# DigitalBlad.net
KiCad netlist of a schematic drawn in Altium Designer
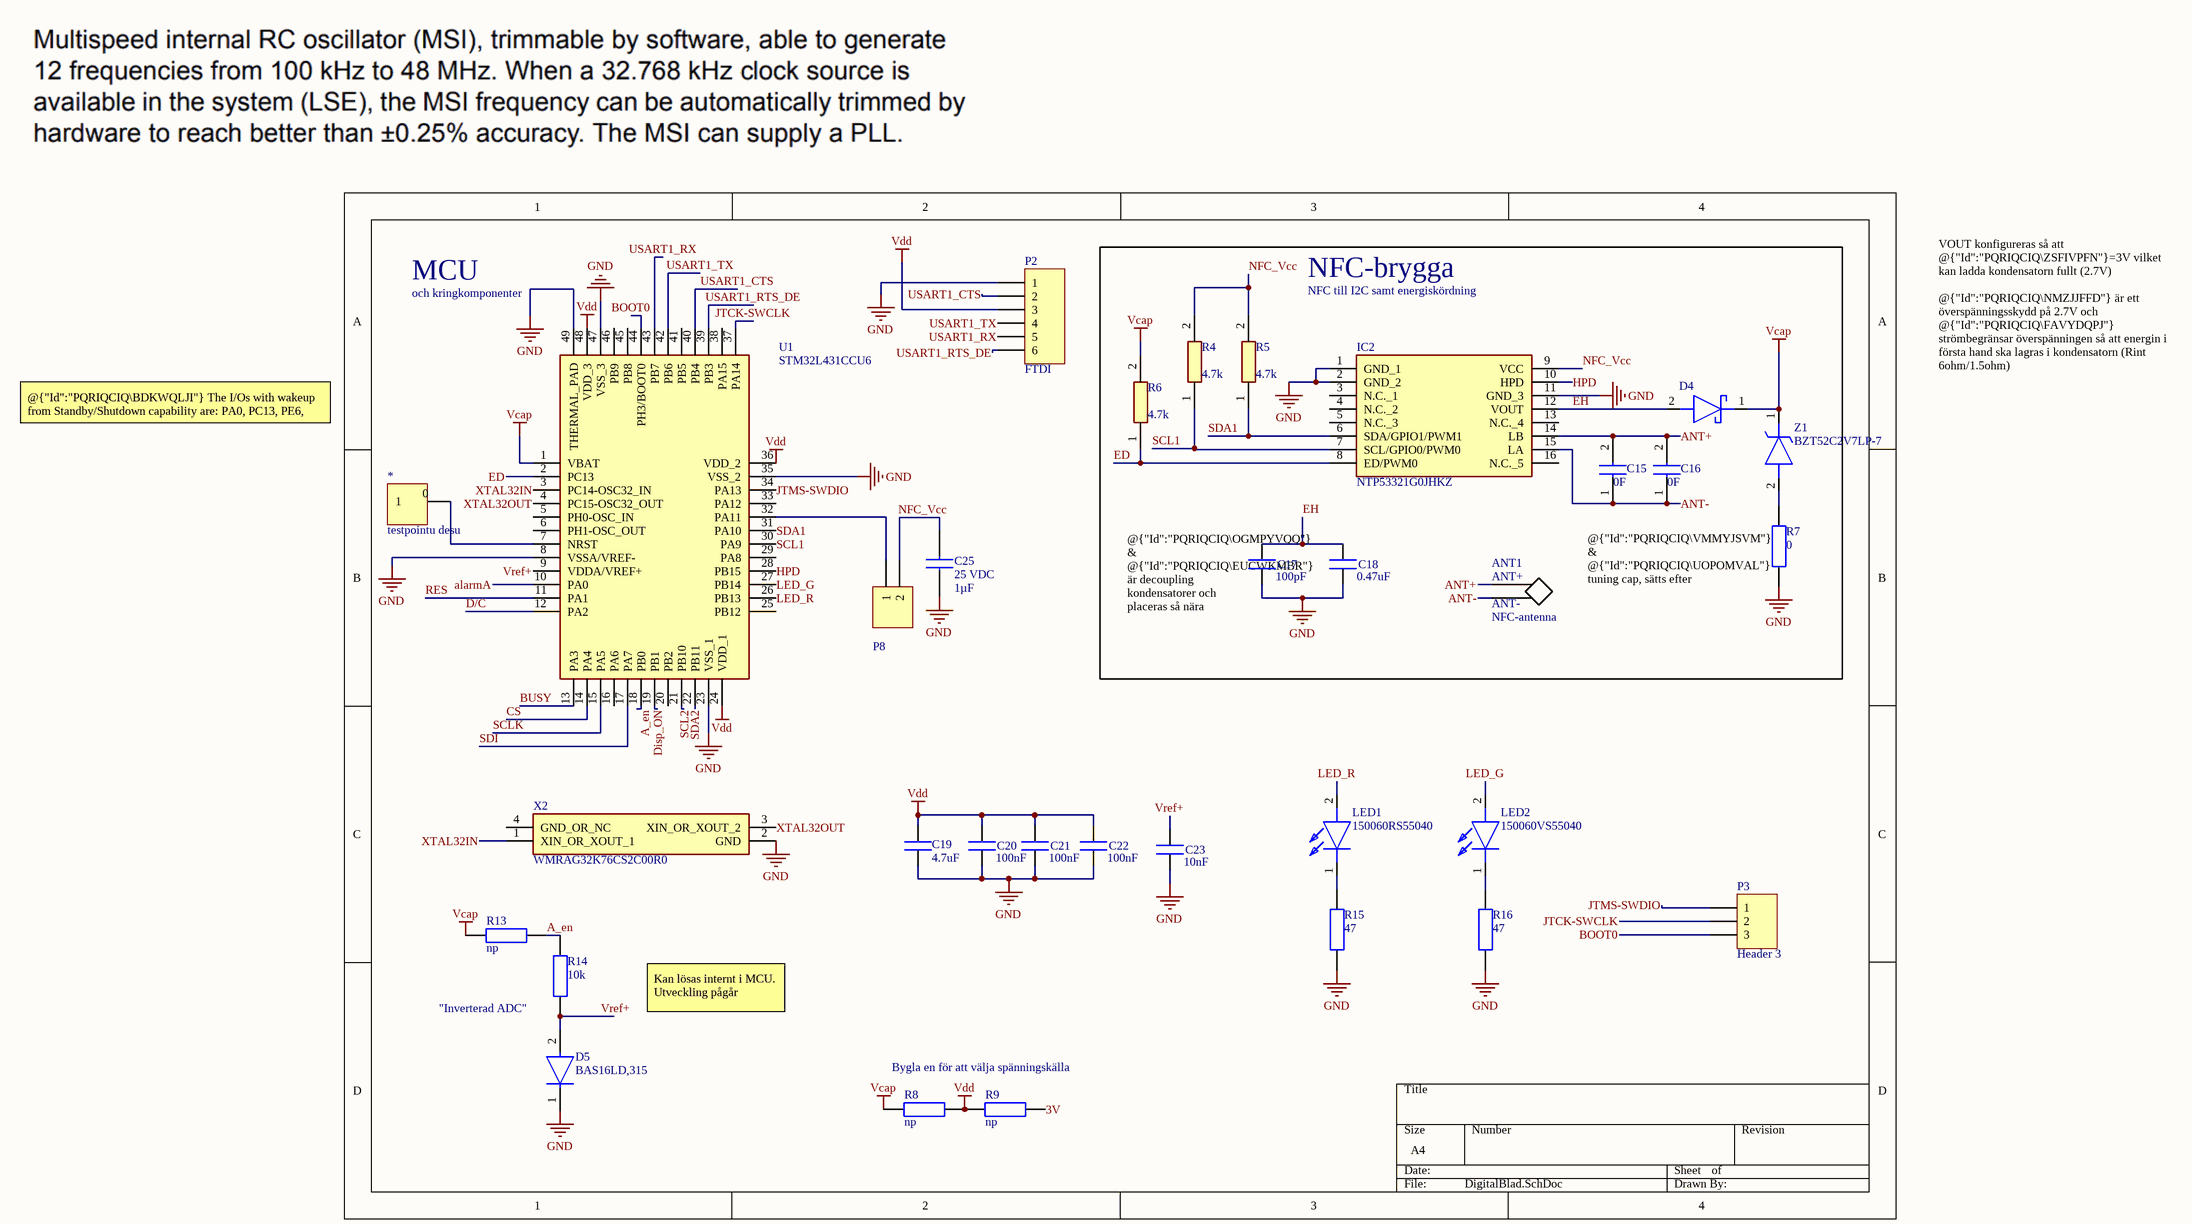
[diagram p0: DigitalBlad.SchDoc]

(export (version "E")
  (design (tool "Eeschema 10.0.6"))
  (components
    (comp (ref "*")
      (value "testpointu desu")
      (footprint "Testupoint")
      (libsource (lib "Schlib") (part "testpointu desu"))
    )
    (comp (ref "ANT1")
      (value "NFC-antenna")
      (footprint "Antenna1")
      (libsource (lib "Schlib") (part "NFC-antenna"))
    )
    (comp (ref "C15")
      (value "0F")
      (footprint "CAPC1005X70N")
      (description "Multilayer Ceramic Capacitors MLCC - SMD/SMT")
      (fields
        (field (name "MOUSER PART NUMBER") "81-GRM155C81C474KE1D")
        (field (name "MANUFACTURER_PART_NUMBER") "GRM155C81C474KE01D")
      )
      (libsource (lib "Linköpings Universitet (SE)") (part "GRM155C81C474KE01D"))
    )
    (comp (ref "C16")
      (value "0F")
      (footprint "CAPC1005X70N")
      (description "Multilayer Ceramic Capacitors MLCC - SMD/SMT")
      (fields
        (field (name "MOUSER PART NUMBER") "81-GRM155C81C474KE1D")
        (field (name "MANUFACTURER_PART_NUMBER") "GRM155C81C474KE01D")
      )
      (libsource (lib "Linköpings Universitet (SE)") (part "GRM155C81C474KE01D"))
    )
    (comp (ref "C17")
      (value "C0402C101KCGACAUTO")
      (footprint "CAPC1005X70N")
      (description "Multilayer Ceramic Capacitors MLCC - SMD/SMT 500V 0.0001uF C0G 0402 10% AEC-Q200")
      (fields (field (name "CAPACITANCE") "100pF"))
      (libsource (lib "Schlib") (part "Generic capacitor"))
    )
    (comp (ref "C18")
      (value "C0402C101KCMBASJ105SB7474KFNA01GACAUTO")
      (footprint "CAPC1005X70N")
      (description "Multilayer Ceramic Capacitors MLCC - SMD/SMT 500V 0.0001uF C0G 0402 10% AEC-Q200")
      (fields (field (name "CAPACITANCE") "0.47uF"))
      (libsource (lib "Schlib") (part "Generic capacitor"))
    )
    (comp (ref "C19")
      (value "C0402C475K8PACTU")
      (footprint "CAPC1005X70N")
      (description "Multilayer Ceramic Capacitors MLCC - SMD/SMT")
      (fields (field (name "CAPACITANCE") "4.7uF"))
      (libsource (lib "Schlib") (part "Generic capacitor"))
    )
    (comp (ref "C20")
      (value "MLAST105SB5104KFNA01")
      (footprint "CAPC1005X70N")
      (description "Multilayer Ceramic Capacitors MLCC - SMD/SMT 25V 0.1uF X5R 0402 10% Medical")
      (fields (field (name "CAPACITANCE") "100nF"))
      (libsource (lib "Schlib") (part "Generic capacitor"))
    )
    (comp (ref "C21")
      (value "MLAST105SB5104KFNA01")
      (footprint "CAPC1005X70N")
      (description "Multilayer Ceramic Capacitors MLCC - SMD/SMT 25V 0.1uF X5R 0402 10% Medical")
      (fields (field (name "CAPACITANCE") "100nF"))
      (libsource (lib "Schlib") (part "Generic capacitor"))
    )
    (comp (ref "C22")
      (value "MLAST105SB5104KFNA01")
      (footprint "CAPC1005X70N")
      (description "Multilayer Ceramic Capacitors MLCC - SMD/SMT 25V 0.1uF X5R 0402 10% Medical")
      (fields (field (name "CAPACITANCE") "100nF"))
      (libsource (lib "Schlib") (part "Generic capacitor"))
    )
    (comp (ref "C23")
      (value "VJ0402Y103KXJAC31X")
      (footprint "CAPC1005X70N")
      (description "Multilayer Ceramic Capacitors MLCC - SMD/SMT 0402 10nF 16volts X7R 10%")
      (fields (field (name "CAPACITANCE") "10nF"))
      (libsource (lib "Schlib") (part "Generic capacitor"))
    )
    (comp (ref "C25")
      (value "1µF")
      (footprint "CAPC1005X55N")
      (description "Capacitor")
      (fields
        (field (name "RATED VOLTAGE") "25 VDC")
        (field (name "MOUSER PART NUMBER") "81-GRM155R61E105KA2D")
        (field (name "ARROW PART NUMBER") "GRM155R61E105KA12D")
      )
      (libsource (lib "Linköpings Universitet (SE)") (part "GRM155R61E105KA12D"))
    )
    (comp (ref "D4")
      (value "RBE01VYM6AFHTR")
      (footprint "RBE01VYM6AFHTR")
      (description "DIODE SCHOTTKY 6V 100MA TUMD2M")
      (fields (field (name "MOUSER PART NUMBER") "755-RBE01VYM6AFHTR"))
      (libsource (lib "Linköpings Universitet (SE)") (part "RBE01VYM6AFHTR"))
    )
    (comp (ref "D5")
      (value "BAS16LD,315")
      (footprint "FP-SOD882D-MFG")
      (description "DIODE GP 100V 215MA SOD882D")
      (fields
        (field (name "MANUFACTURER") "Nexperia")
        (field (name "OCTOPART") "https://octopart.com/bas16ld%2C315-nexperia-78753474")
      )
      (libsource (lib "Altium Content Vault") (part "ac0aaae217eb7629c2018f89389cb6d"))
    )
    (comp (ref "IC2")
      (value "NTP53321G0JHKZ")
      (footprint "NTP53321G0JHKZ")
      (description "Interface - Specialized NTAG")
      (fields (field (name "MOUSER PART NUMBER") "771-NTP53321G0JHKZ"))
      (libsource (lib "Linköpings Universitet (SE)") (part "NTP53321G0JHKZ"))
    )
    (comp (ref "LED1")
      (value "150060RS55040")
      (footprint "150060RS55040")
      (description "RED Standard LEDs - SMD WL-SMCD SMD MonoChip 0603 Red 632nm")
      (fields (field (name "MOUSER PART NUMBER") "710-150060RS55040"))
      (libsource (lib "Linköpings Universitet (SE)") (part "150060VS55040"))
    )
    (comp (ref "LED2")
      (value "150060VS55040")
      (footprint "LEDM168X50N")
      (description "Green LED")
      (fields (field (name "MOUSER PART NUMBER") "710-150060VS55040"))
      (libsource (lib "Linköpings Universitet (SE)") (part "150060VS55040"))
    )
    (comp (ref "P2")
      (value "FTDI")
      (footprint "HDR1X6")
      (description "Header, 6-Pin")
      (fields (field (name "PUBLISHER") "Altium Limited"))
      (libsource (lib "Linköpings Universitet (SE)") (part "Header 6H"))
    )
    (comp (ref "P3")
      (value "Header 3")
      (footprint "HDR1X3")
      (description "Header, 3-Pin")
      (fields (field (name "PUBLISHER") "Altium Limited"))
      (libsource (lib "Linköpings Universitet (SE)") (part "Header 3H"))
    )
    (comp (ref "P8")
      (value "Header 2")
      (footprint "HDR1X2")
      (description "Header, 2-Pin")
      (fields (field (name "PUBLISHER") "Altium Limited"))
      (libsource (lib "Linköpings Universitet (SE)") (part "Header 2H"))
    )
    (comp (ref "R4")
      (value "CRCW04024K70FKEDHP")
      (footprint "RESC1005X40N")
      (fields (field (name "MOUSER PART NUMBER") "71-CRCW04024K70FKEDH") (field (name "RESISTANCE") "4.7k"))
      (libsource (lib "Linköpings Universitet (SE)") (part "CRCW04024K70FKEDHP"))
    )
    (comp (ref "R5")
      (value "CRCW04024K70FKEDHP")
      (footprint "RESC1005X40N")
      (fields (field (name "MOUSER PART NUMBER") "71-CRCW04024K70FKEDH") (field (name "RESISTANCE") "4.7k"))
      (libsource (lib "Linköpings Universitet (SE)") (part "CRCW04024K70FKEDHP"))
    )
    (comp (ref "R6")
      (value "CRCW04024K70FKEDHP")
      (footprint "RESC1005X40N")
      (fields (field (name "MOUSER PART NUMBER") "71-CRCW04024K70FKEDH") (field (name "RESISTANCE") "4.7k"))
      (libsource (lib "Linköpings Universitet (SE)") (part "CRCW04024K70FKEDHP"))
    )
    (comp (ref "R7")
      (value "SFR01MZPJ470")
      (footprint "RESC1005X40N")
      (description "Thick Film Resistors Sulfur Tolerant Chip Resistors 0402 case size")
      (fields (field (name "RESISTANCE") "0"))
      (libsource (lib "Schlib") (part "Generic resistor"))
    )
    (comp (ref "R8")
      (value "Generic component")
      (footprint "RESC1005X40N")
      (fields (field (name "RESISTANCE") "np"))
      (libsource (lib "") (part "Generic resistor_2"))
    )
    (comp (ref "R9")
      (value "Generic component")
      (footprint "RESC1005X40N")
      (fields (field (name "RESISTANCE") "np"))
      (libsource (lib "") (part "Generic resistor_2"))
    )
    (comp (ref "R13")
      (value "Generic component")
      (footprint "RESC1005X40N")
      (fields (field (name "RESISTANCE") "np"))
      (libsource (lib "") (part "Generic resistor_2"))
    )
    (comp (ref "R14")
      (value "CRCW04024K70FKEDHP")
      (footprint "RESC1005X40N")
      (fields (field (name "RESISTANCE") "10k"))
      (libsource (lib "") (part "Generic resistor_1"))
    )
    (comp (ref "R15")
      (value "SFR01MZPJ470")
      (footprint "RESC1005X40N")
      (description "Thick Film Resistors Sulfur Tolerant Chip Resistors 0402 case size")
      (fields (field (name "RESISTANCE") "47"))
      (libsource (lib "") (part "Generic resistor_1"))
    )
    (comp (ref "R16")
      (value "SFR01MZPJ470")
      (footprint "RESC1005X40N")
      (description "Thick Film Resistors Sulfur Tolerant Chip Resistors 0402 case size")
      (fields (field (name "RESISTANCE") "47"))
      (libsource (lib "") (part "Generic resistor_1"))
    )
    (comp (ref "U1")
      (value "STM32L431CCU6")
      (footprint "QFN50P700X700X60-49N-D")
      (description "ARM Microcontrollers - MCU 16/32-BITS MICROS")
      (fields (field (name "MOUSER PART NUMBER") "511-STM32L431CCU6"))
      (libsource (lib "Linköpings Universitet (SE)") (part "STM32L431CCU6"))
    )
    (comp (ref "X2")
      (value "WMRAG32K76CS2C00R0")
      (footprint "WMRAG32K76CS2C00R0")
      (description "32.768 kHz +/-20ppm Crystal 8pF 75 kOhms 4-SMD")
      (fields (field (name "MOUSER PART NUMBER") "81-WMRAG32K76CS2C00R"))
      (libsource (lib "Linköpings Universitet (SE)") (part "WMRAG32K76CS2C00R0"))
    )
    (comp (ref "Z1")
      (value "BZT52C2V7LP-7")
      (footprint "BZT52C2V7LP7")
      (description "Zener Diode 2.7 V 250 mW +/-7% Surface Mount DFN1006-2")
      (fields (field (name "MOUSER PART NUMBER") "621-BZT52C2V7LP-7"))
      (libsource (lib "Linköpings Universitet (SE)") (part "BZT52C2V7LP-7"))
    )
  )
  (nets
    (net (code "1") (name "/3V") (class "Default")
      (node (ref "R9") (pin "1") (pinfunction "1_1") (pintype "passive"))
    )
    (net (code "2") (name "/ANT+") (class "Default")
      (node (ref "ANT1") (pin "1") (pinfunction "+_1") (pintype "passive"))
      (node (ref "C15") (pin "2") (pinfunction "2_2") (pintype "passive"))
      (node (ref "C16") (pin "2") (pinfunction "2_2") (pintype "passive"))
      (node (ref "IC2") (pin "14") (pinfunction "LB_14") (pintype "passive"))
    )
    (net (code "3") (name "/ANT-") (class "Default")
      (node (ref "ANT1") (pin "1") (pinfunction "-_1") (pintype "passive"))
      (node (ref "C15") (pin "1") (pinfunction "1_1") (pintype "passive"))
      (node (ref "C16") (pin "1") (pinfunction "1_1") (pintype "passive"))
      (node (ref "IC2") (pin "15") (pinfunction "LA_15") (pintype "passive"))
    )
    (net (code "4") (name "/A_en") (class "Default")
      (node (ref "R13") (pin "1") (pinfunction "1_1") (pintype "passive"))
      (node (ref "R14") (pin "2") (pinfunction "2_2") (pintype "passive"))
      (node (ref "U1") (pin "18") (pinfunction "PB0_18") (pintype "passive"))
    )
    (net (code "5") (name "/BOOT0") (class "Default")
      (node (ref "P3") (pin "3") (pinfunction "3_3") (pintype "passive"))
      (node (ref "U1") (pin "44") (pinfunction "PH3/BOOT0_44") (pintype "passive"))
    )
    (net (code "6") (name "/BUSY") (class "Default")
      (node (ref "U1") (pin "13") (pinfunction "PA3_13") (pintype "passive"))
    )
    (net (code "7") (name "/CS") (class "Default")
      (node (ref "U1") (pin "14") (pinfunction "PA4_14") (pintype "passive"))
    )
    (net (code "8") (name "/Disp_ON") (class "Default")
      (node (ref "U1") (pin "19") (pinfunction "PB1_19") (pintype "passive"))
    )
    (net (code "9") (name "/D{slash}C") (class "Default")
      (node (ref "U1") (pin "12") (pinfunction "PA2_12") (pintype "passive"))
    )
    (net (code "10") (name "/ED") (class "Default")
      (node (ref "IC2") (pin "8") (pinfunction "ED/PWM0_8") (pintype "passive"))
      (node (ref "R6") (pin "1") (pinfunction "1_1") (pintype "passive"))
      (node (ref "U1") (pin "2") (pinfunction "PC13_2") (pintype "passive"))
    )
    (net (code "11") (name "/EH") (class "Default")
      (node (ref "C17") (pin "2") (pinfunction "2_2") (pintype "passive"))
      (node (ref "C18") (pin "2") (pinfunction "2_2") (pintype "passive"))
      (node (ref "D4") (pin "2") (pinfunction "A_2") (pintype "passive"))
      (node (ref "IC2") (pin "12") (pinfunction "VOUT_12") (pintype "passive"))
    )
    (net (code "12") (name "/HPD") (class "Default")
      (node (ref "IC2") (pin "10") (pinfunction "HPD_10") (pintype "passive"))
      (node (ref "U1") (pin "28") (pinfunction "PB15_28") (pintype "passive"))
    )
    (net (code "13") (name "/JTCK-SWCLK") (class "Default")
      (node (ref "P3") (pin "2") (pinfunction "2_2") (pintype "passive"))
      (node (ref "U1") (pin "37") (pinfunction "PA14_37") (pintype "passive"))
    )
    (net (code "14") (name "/JTMS-SWDIO") (class "Default")
      (node (ref "P3") (pin "1") (pinfunction "1_1") (pintype "passive"))
      (node (ref "U1") (pin "34") (pinfunction "PA13_34") (pintype "passive"))
    )
    (net (code "15") (name "/LED_G") (class "Default")
      (node (ref "LED2") (pin "2") (pinfunction "A_2") (pintype "passive"))
      (node (ref "U1") (pin "27") (pinfunction "PB14_27") (pintype "passive"))
    )
    (net (code "16") (name "/LED_R") (class "Default")
      (node (ref "LED1") (pin "2") (pinfunction "A_2") (pintype "passive"))
      (node (ref "U1") (pin "26") (pinfunction "PB13_26") (pintype "passive"))
    )
    (net (code "17") (name "/NFC_Vcc") (class "Default")
      (node (ref "C25") (pin "1") (pinfunction "1_1") (pintype "passive"))
      (node (ref "IC2") (pin "9") (pinfunction "VCC_9") (pintype "passive"))
      (node (ref "P8") (pin "2") (pinfunction "2_2") (pintype "passive"))
      (node (ref "R4") (pin "2") (pinfunction "2_2") (pintype "passive"))
      (node (ref "R5") (pin "2") (pinfunction "2_2") (pintype "passive"))
    )
    (net (code "18") (name "/RES") (class "Default")
      (node (ref "U1") (pin "11") (pinfunction "PA1_11") (pintype "passive"))
    )
    (net (code "19") (name "/SCL1") (class "Default")
      (node (ref "IC2") (pin "7") (pinfunction "SCL/GPIO0/PWM0_7") (pintype "passive"))
      (node (ref "R4") (pin "1") (pinfunction "1_1") (pintype "passive"))
      (node (ref "U1") (pin "30") (pinfunction "PA9_30") (pintype "passive"))
    )
    (net (code "20") (name "/SCL2") (class "Default")
      (node (ref "U1") (pin "21") (pinfunction "PB10_21") (pintype "passive"))
    )
    (net (code "21") (name "/SCLK") (class "Default")
      (node (ref "U1") (pin "15") (pinfunction "PA5_15") (pintype "passive"))
    )
    (net (code "22") (name "/SDA1") (class "Default")
      (node (ref "IC2") (pin "6") (pinfunction "SDA/GPIO1/PWM1_6") (pintype "passive"))
      (node (ref "R5") (pin "1") (pinfunction "1_1") (pintype "passive"))
      (node (ref "U1") (pin "31") (pinfunction "PA10_31") (pintype "passive"))
    )
    (net (code "23") (name "/SDA2") (class "Default")
      (node (ref "U1") (pin "22") (pinfunction "PB11_22") (pintype "passive"))
    )
    (net (code "24") (name "/SDI") (class "Default")
      (node (ref "U1") (pin "17") (pinfunction "PA7_17") (pintype "passive"))
    )
    (net (code "25") (name "/USART1_CTS") (class "Default")
      (node (ref "P2") (pin "2") (pinfunction "2_2") (pintype "passive"))
      (node (ref "U1") (pin "40") (pinfunction "PB4_40") (pintype "passive"))
    )
    (net (code "26") (name "/USART1_RTS_DE") (class "Default")
      (node (ref "P2") (pin "6") (pinfunction "6_6") (pintype "passive"))
      (node (ref "U1") (pin "39") (pinfunction "PB3_39") (pintype "passive"))
    )
    (net (code "27") (name "/USART1_RX") (class "Default")
      (node (ref "P2") (pin "5") (pinfunction "5_5") (pintype "passive"))
      (node (ref "U1") (pin "43") (pinfunction "PB7_43") (pintype "passive"))
    )
    (net (code "28") (name "/USART1_TX") (class "Default")
      (node (ref "P2") (pin "4") (pinfunction "4_4") (pintype "passive"))
      (node (ref "U1") (pin "42") (pinfunction "PB6_42") (pintype "passive"))
    )
    (net (code "29") (name "/Vref+") (class "Default")
      (node (ref "C23") (pin "1") (pinfunction "1_1") (pintype "passive"))
      (node (ref "D5") (pin "2") (pinfunction "A_2") (pintype "passive"))
      (node (ref "R14") (pin "1") (pinfunction "1_1") (pintype "passive"))
      (node (ref "U1") (pin "9") (pinfunction "VDDA/VREF+_9") (pintype "passive"))
    )
    (net (code "30") (name "/XTAL32IN") (class "Default")
      (node (ref "U1") (pin "3") (pinfunction "PC14-OSC32_IN_3") (pintype "passive"))
      (node (ref "X2") (pin "1") (pinfunction "XIN_OR_XOUT_1_1") (pintype "passive"))
    )
    (net (code "31") (name "/XTAL32OUT") (class "Default")
      (node (ref "U1") (pin "4") (pinfunction "PC15-OSC32_OUT_4") (pintype "passive"))
      (node (ref "X2") (pin "3") (pinfunction "XIN_OR_XOUT_2_3") (pintype "passive"))
    )
    (net (code "32") (name "/alarmA") (class "Default")
      (node (ref "U1") (pin "10") (pinfunction "PA0_10") (pintype "passive"))
    )
    (net (code "33") (name "GND") (class "Default")
      (node (ref "C17") (pin "1") (pinfunction "1_1") (pintype "passive"))
      (node (ref "C18") (pin "1") (pinfunction "1_1") (pintype "passive"))
      (node (ref "C19") (pin "2") (pinfunction "2_2") (pintype "passive"))
      (node (ref "C20") (pin "2") (pinfunction "2_2") (pintype "passive"))
      (node (ref "C21") (pin "2") (pinfunction "2_2") (pintype "passive"))
      (node (ref "C22") (pin "2") (pinfunction "2_2") (pintype "passive"))
      (node (ref "C23") (pin "2") (pinfunction "2_2") (pintype "passive"))
      (node (ref "C25") (pin "2") (pinfunction "2_2") (pintype "passive"))
      (node (ref "D5") (pin "1") (pinfunction "C_1") (pintype "passive"))
      (node (ref "IC2") (pin "1") (pinfunction "GND_1_1") (pintype "passive"))
      (node (ref "IC2") (pin "11") (pinfunction "GND_3_11") (pintype "passive"))
      (node (ref "IC2") (pin "2") (pinfunction "GND_2_2") (pintype "passive"))
      (node (ref "P2") (pin "1") (pinfunction "1_1") (pintype "passive"))
      (node (ref "R15") (pin "1") (pinfunction "1_1") (pintype "passive"))
      (node (ref "R16") (pin "1") (pinfunction "1_1") (pintype "passive"))
      (node (ref "R7") (pin "2") (pinfunction "2_2") (pintype "passive"))
      (node (ref "U1") (pin "23") (pinfunction "VSS_1_23") (pintype "passive"))
      (node (ref "U1") (pin "35") (pinfunction "VSS_2_35") (pintype "passive"))
      (node (ref "U1") (pin "47") (pinfunction "VSS_3_47") (pintype "passive"))
      (node (ref "U1") (pin "49") (pinfunction "THERMAL_PAD_49") (pintype "passive"))
      (node (ref "U1") (pin "8") (pinfunction "VSSA/VREF-_8") (pintype "passive"))
      (node (ref "X2") (pin "2") (pinfunction "GND_2") (pintype "passive"))
    )
    (net (code "34") (name "Net-(*-1)") (class "Default")
      (node (ref "*") (pin "0") (pinfunction "1_0") (pintype "passive"))
      (node (ref "U1") (pin "7") (pinfunction "NRST_7") (pintype "passive"))
    )
    (net (code "35") (name "Net-(LED1-K)") (class "Default")
      (node (ref "LED1") (pin "1") (pinfunction "K_1") (pintype "passive"))
      (node (ref "R15") (pin "2") (pinfunction "2_2") (pintype "passive"))
    )
    (net (code "36") (name "Net-(LED2-K)") (class "Default")
      (node (ref "LED2") (pin "1") (pinfunction "K_1") (pintype "passive"))
      (node (ref "R16") (pin "2") (pinfunction "2_2") (pintype "passive"))
    )
    (net (code "37") (name "Net-(U1-PA11)") (class "Default")
      (node (ref "P8") (pin "1") (pinfunction "1_1") (pintype "passive"))
      (node (ref "U1") (pin "32") (pinfunction "PA11_32") (pintype "passive"))
    )
    (net (code "38") (name "Net-(Z1-A)") (class "Default")
      (node (ref "R7") (pin "1") (pinfunction "1_1") (pintype "passive"))
      (node (ref "Z1") (pin "2") (pinfunction "A_2") (pintype "passive"))
    )
    (net (code "39") (name "Vcap") (class "Default")
      (node (ref "D4") (pin "1") (pinfunction "K_1") (pintype "passive"))
      (node (ref "R13") (pin "2") (pinfunction "2_2") (pintype "passive"))
      (node (ref "R6") (pin "2") (pinfunction "2_2") (pintype "passive"))
      (node (ref "R8") (pin "2") (pinfunction "2_2") (pintype "passive"))
      (node (ref "U1") (pin "1") (pinfunction "VBAT_1") (pintype "passive"))
      (node (ref "Z1") (pin "1") (pinfunction "K_1") (pintype "passive"))
    )
    (net (code "40") (name "Vdd") (class "Default")
      (node (ref "C19") (pin "1") (pinfunction "1_1") (pintype "passive"))
      (node (ref "C20") (pin "1") (pinfunction "1_1") (pintype "passive"))
      (node (ref "C21") (pin "1") (pinfunction "1_1") (pintype "passive"))
      (node (ref "C22") (pin "1") (pinfunction "1_1") (pintype "passive"))
      (node (ref "P2") (pin "3") (pinfunction "3_3") (pintype "passive"))
      (node (ref "R8") (pin "1") (pinfunction "1_1") (pintype "passive"))
      (node (ref "R9") (pin "2") (pinfunction "2_2") (pintype "passive"))
      (node (ref "U1") (pin "24") (pinfunction "VDD_1_24") (pintype "passive"))
      (node (ref "U1") (pin "36") (pinfunction "VDD_2_36") (pintype "passive"))
      (node (ref "U1") (pin "48") (pinfunction "VDD_3_48") (pintype "passive"))
    )
    (net (code "41") (name "unconnected-(IC2-N.C._1-Pad3)") (class "Default")
      (node (ref "IC2") (pin "3") (pinfunction "N.C._1_3") (pintype "passive"))
    )
    (net (code "42") (name "unconnected-(IC2-N.C._2-Pad4)") (class "Default")
      (node (ref "IC2") (pin "4") (pinfunction "N.C._2_4") (pintype "passive"))
    )
    (net (code "43") (name "unconnected-(IC2-N.C._3-Pad5)") (class "Default")
      (node (ref "IC2") (pin "5") (pinfunction "N.C._3_5") (pintype "passive"))
    )
    (net (code "44") (name "unconnected-(IC2-N.C._4-Pad13)") (class "Default")
      (node (ref "IC2") (pin "13") (pinfunction "N.C._4_13") (pintype "passive"))
    )
    (net (code "45") (name "unconnected-(IC2-N.C._5-Pad16)") (class "Default")
      (node (ref "IC2") (pin "16") (pinfunction "N.C._5_16") (pintype "passive"))
    )
    (net (code "46") (name "unconnected-(U1-PA6-Pad16)") (class "Default")
      (node (ref "U1") (pin "16") (pinfunction "PA6_16") (pintype "passive"))
    )
    (net (code "47") (name "unconnected-(U1-PA8-Pad29)") (class "Default")
      (node (ref "U1") (pin "29") (pinfunction "PA8_29") (pintype "passive"))
    )
    (net (code "48") (name "unconnected-(U1-PA12-Pad33)") (class "Default")
      (node (ref "U1") (pin "33") (pinfunction "PA12_33") (pintype "passive"))
    )
    (net (code "49") (name "unconnected-(U1-PA15-Pad38)") (class "Default")
      (node (ref "U1") (pin "38") (pinfunction "PA15_38") (pintype "passive"))
    )
    (net (code "50") (name "unconnected-(U1-PB2-Pad20)") (class "Default")
      (node (ref "U1") (pin "20") (pinfunction "PB2_20") (pintype "passive"))
    )
    (net (code "51") (name "unconnected-(U1-PB5-Pad41)") (class "Default")
      (node (ref "U1") (pin "41") (pinfunction "PB5_41") (pintype "passive"))
    )
    (net (code "52") (name "unconnected-(U1-PB8-Pad45)") (class "Default")
      (node (ref "U1") (pin "45") (pinfunction "PB8_45") (pintype "passive"))
    )
    (net (code "53") (name "unconnected-(U1-PB9-Pad46)") (class "Default")
      (node (ref "U1") (pin "46") (pinfunction "PB9_46") (pintype "passive"))
    )
    (net (code "54") (name "unconnected-(U1-PB12-Pad25)") (class "Default")
      (node (ref "U1") (pin "25") (pinfunction "PB12_25") (pintype "passive"))
    )
    (net (code "55") (name "unconnected-(U1-PH0-OSC_IN-Pad5)") (class "Default")
      (node (ref "U1") (pin "5") (pinfunction "PH0-OSC_IN_5") (pintype "passive"))
    )
    (net (code "56") (name "unconnected-(U1-PH1-OSC_OUT-Pad6)") (class "Default")
      (node (ref "U1") (pin "6") (pinfunction "PH1-OSC_OUT_6") (pintype "passive"))
    )
    (net (code "57") (name "unconnected-(X2-GND_OR_NC-Pad4)") (class "Default")
      (node (ref "X2") (pin "4") (pinfunction "GND_OR_NC_4") (pintype "passive"))
    )
  )
)
